# vssb_SMD.net
KiCad netlist of a schematic drawn in EAGLE
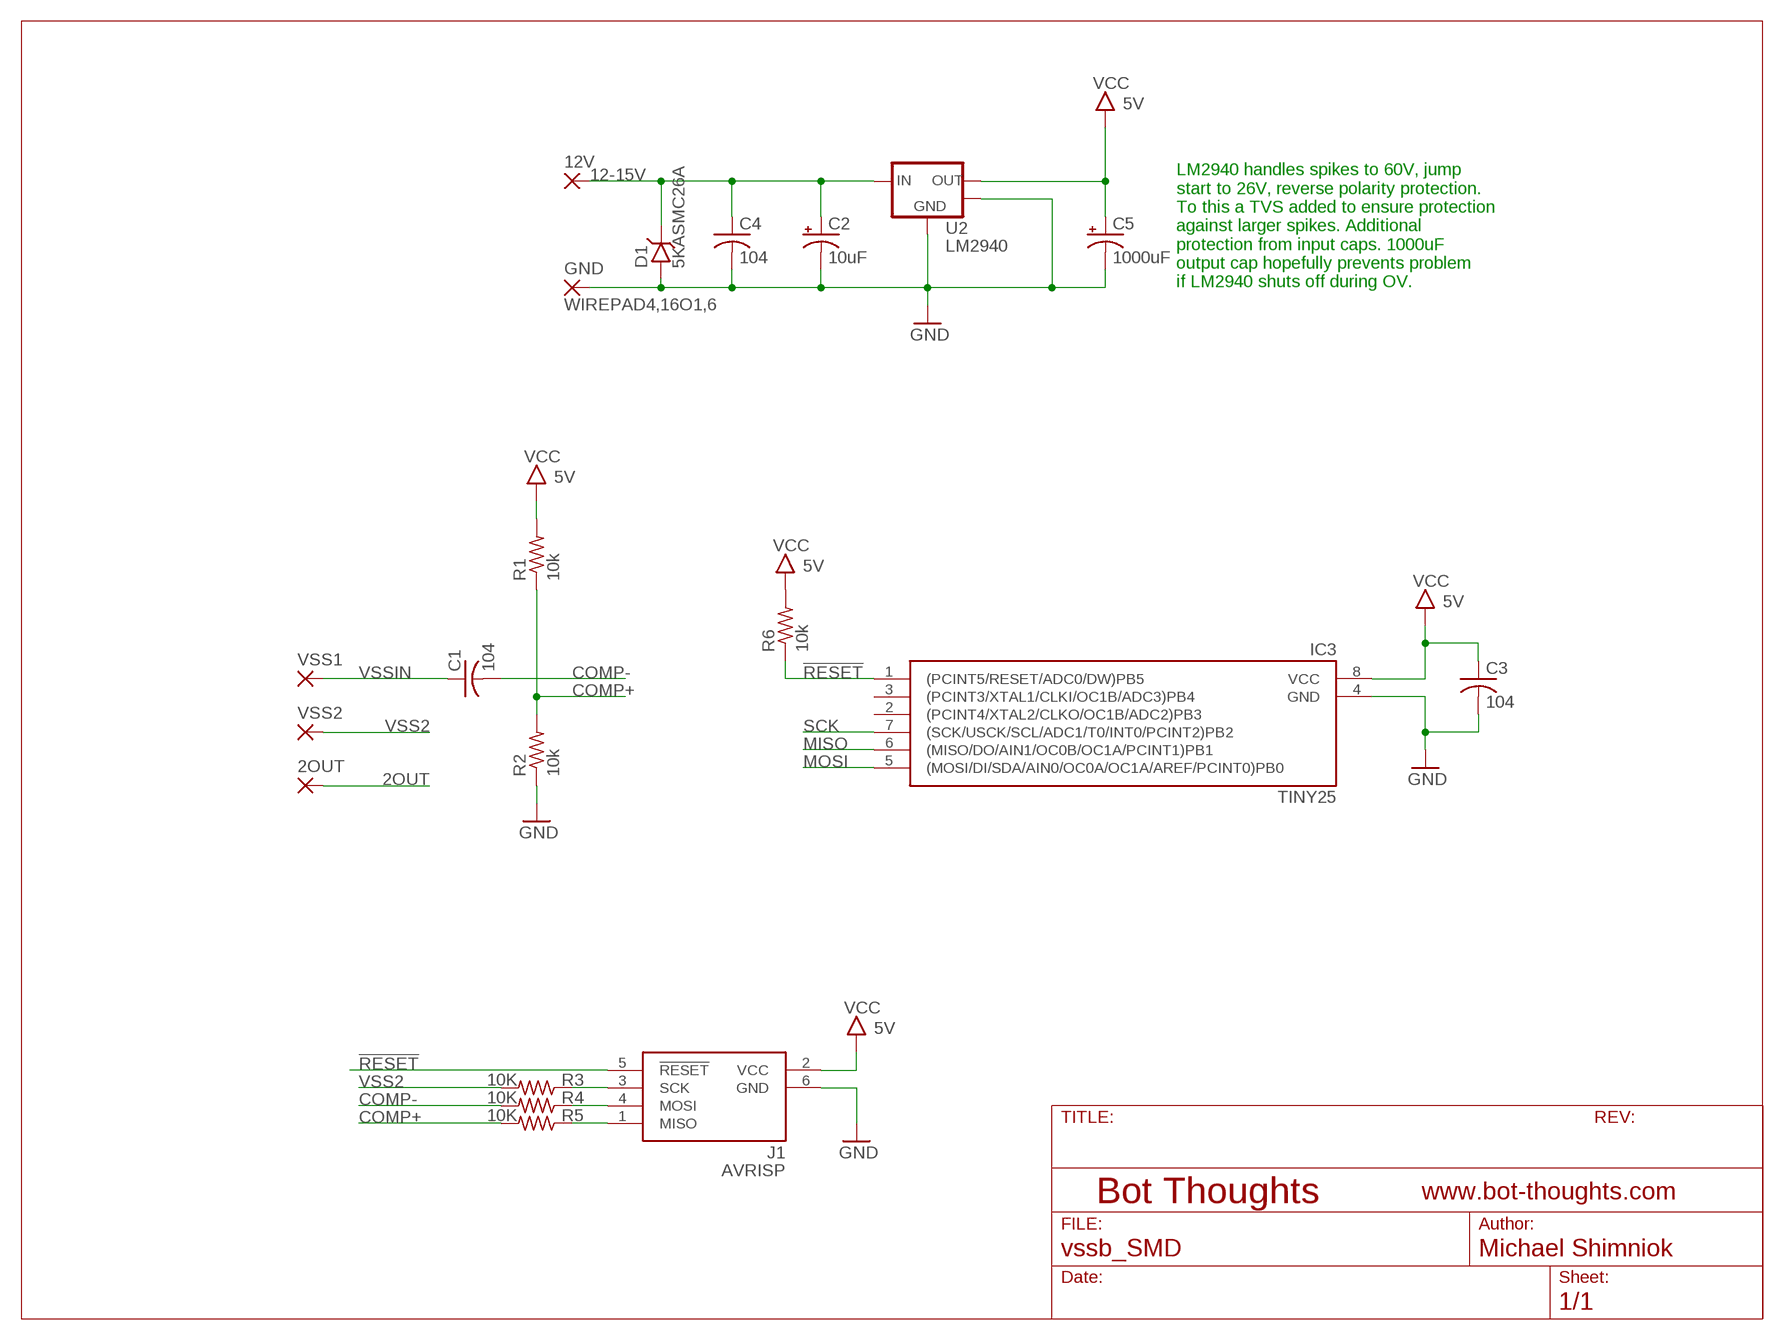
[diagram p0: schematic, sheet 1]

(export (version "E")
  (design (tool "Eeschema 10.0.6"))
  (components
    (comp (ref "2OUT")
      (value "WIREPAD4,16O1,6")
      (footprint "eagle-import:4,16O1,6")
      (libsource (lib "eagle-import") (part "WIREPAD4,16O1,6"))
    )
    (comp (ref "12V")
      (value "WIREPAD4,16O1,6")
      (footprint "eagle-import:4,16O1,6")
      (libsource (lib "eagle-import") (part "WIREPAD4,16O1,6"))
    )
    (comp (ref "C1")
      (value "104")
      (footprint "eagle-import:C0603")
      (libsource (lib "eagle-import") (part "C-USC0603"))
    )
    (comp (ref "C2")
      (value "10uF")
      (footprint "eagle-import:E2,5-6")
      (libsource (lib "eagle-import") (part "CPOL-USE2.5-6"))
    )
    (comp (ref "C3")
      (value "104")
      (footprint "eagle-import:C0603")
      (libsource (lib "eagle-import") (part "C-USC0603"))
    )
    (comp (ref "C4")
      (value "104")
      (footprint "eagle-import:C0603")
      (libsource (lib "eagle-import") (part "C-USC0603"))
    )
    (comp (ref "C5")
      (value "1000uF")
      (footprint "eagle-import:E5-13")
      (libsource (lib "eagle-import") (part "CPOL-USE5-13"))
    )
    (comp (ref "D1")
      (value "5KASMC26A")
      (footprint "eagle-import:DO-214AB")
      (libsource (lib "eagle-import") (part "5KASMC"))
    )
    (comp (ref "GND")
      (value "WIREPAD4,16O1,6")
      (footprint "eagle-import:4,16O1,6")
      (libsource (lib "eagle-import") (part "WIREPAD4,16O1,6"))
    )
    (comp (ref "IC3")
      (value "TINY25")
      (footprint "eagle-import:SOIC8N")
      (libsource (lib "eagle-import") (part "TINY25/45/85-20SSU"))
    )
    (comp (ref "J1")
      (value "AVRISP")
      (footprint "eagle-import:CON6P2R")
      (libsource (lib "eagle-import") (part "AVRISP6_COMPACT"))
    )
    (comp (ref "R1")
      (value "10k")
      (footprint "eagle-import:R0603")
      (libsource (lib "eagle-import") (part "R-US_R0603"))
    )
    (comp (ref "R2")
      (value "10k")
      (footprint "eagle-import:R0603")
      (libsource (lib "eagle-import") (part "R-US_R0603"))
    )
    (comp (ref "R3")
      (value "10K")
      (footprint "eagle-import:R0603")
      (libsource (lib "eagle-import") (part "R-US_R0603"))
    )
    (comp (ref "R4")
      (value "10K")
      (footprint "eagle-import:R0603")
      (libsource (lib "eagle-import") (part "R-US_R0603"))
    )
    (comp (ref "R5")
      (value "10K")
      (footprint "eagle-import:R0603")
      (libsource (lib "eagle-import") (part "R-US_R0603"))
    )
    (comp (ref "R6")
      (value "10k")
      (footprint "eagle-import:R0603")
      (libsource (lib "eagle-import") (part "R-US_R0603"))
    )
    (comp (ref "U2")
      (value "LM2940")
      (footprint "eagle-import:SOT-223-3")
      (libsource (lib "eagle-import") (part "LM2940DCY"))
    )
    (comp (ref "VSS1")
      (value "WIREPAD4,16O1,6")
      (footprint "eagle-import:4,16O1,6")
      (libsource (lib "eagle-import") (part "WIREPAD4,16O1,6"))
    )
    (comp (ref "VSS2")
      (value "WIREPAD4,16O1,6")
      (footprint "eagle-import:4,16O1,6")
      (libsource (lib "eagle-import") (part "WIREPAD4,16O1,6"))
    )
  )
  (nets
    (net (code "1") (name "/2OUT") (class "Default")
      (node (ref "2OUT") (pin "1") (pinfunction "P_1") (pintype "passive"))
    )
    (net (code "2") (name "/12-15V") (class "Default")
      (node (ref "12V") (pin "1") (pinfunction "P_1") (pintype "passive"))
      (node (ref "C2") (pin "+") (pinfunction "+_+") (pintype "passive"))
      (node (ref "C4") (pin "1") (pinfunction "1_1") (pintype "passive"))
      (node (ref "D1") (pin "C") (pinfunction "C_C") (pintype "passive"))
      (node (ref "U2") (pin "1") (pinfunction "VIN_1") (pintype "bidirectional"))
    )
    (net (code "3") (name "/COMP+") (class "Default")
      (node (ref "R1") (pin "1") (pinfunction "1_1") (pintype "passive"))
      (node (ref "R2") (pin "2") (pinfunction "2_2") (pintype "passive"))
      (node (ref "R5") (pin "2") (pinfunction "2_2") (pintype "passive"))
    )
    (net (code "4") (name "/COMP-") (class "Default")
      (node (ref "C1") (pin "2") (pinfunction "2_2") (pintype "passive"))
      (node (ref "R4") (pin "2") (pinfunction "2_2") (pintype "passive"))
    )
    (net (code "5") (name "/MISO") (class "Default")
      (node (ref "IC3") (pin "6") (pinfunction "(MISO/DO/AIN1/OC0B/OC1A/PCINT1)PB1_6") (pintype "bidirectional"))
      (node (ref "J1") (pin "1") (pinfunction "MISO_1") (pintype "input"))
      (node (ref "R5") (pin "1") (pinfunction "1_1") (pintype "passive"))
    )
    (net (code "6") (name "/MOSI") (class "Default")
      (node (ref "IC3") (pin "5") (pinfunction "(MOSI/DI/SDA/AIN0/OC0A/OC1A/AREF/PCINT0)PB0_5") (pintype "bidirectional"))
      (node (ref "J1") (pin "4") (pinfunction "MOSI_4") (pintype "output"))
      (node (ref "R4") (pin "1") (pinfunction "1_1") (pintype "passive"))
    )
    (net (code "7") (name "/SCK") (class "Default")
      (node (ref "IC3") (pin "7") (pinfunction "(SCK/USCK/SCL/ADC1/T0/INT0/PCINT2)PB2_7") (pintype "bidirectional"))
      (node (ref "J1") (pin "3") (pinfunction "SCK_3") (pintype "output"))
      (node (ref "R3") (pin "1") (pinfunction "1_1") (pintype "passive"))
    )
    (net (code "8") (name "/VSS2") (class "Default")
      (node (ref "R3") (pin "2") (pinfunction "2_2") (pintype "passive"))
      (node (ref "VSS2") (pin "1") (pinfunction "P_1") (pintype "passive"))
    )
    (net (code "9") (name "/VSSIN") (class "Default")
      (node (ref "C1") (pin "1") (pinfunction "1_1") (pintype "passive"))
      (node (ref "VSS1") (pin "1") (pinfunction "P_1") (pintype "passive"))
    )
    (net (code "10") (name "/~{RESET}") (class "Default")
      (node (ref "IC3") (pin "1") (pinfunction "(PCINT5/RESET/ADC0/DW)PB5_1") (pintype "bidirectional"))
      (node (ref "J1") (pin "5") (pinfunction "~{RESET}_5") (pintype "output"))
      (node (ref "R6") (pin "1") (pinfunction "1_1") (pintype "passive"))
    )
    (net (code "11") (name "5V") (class "Default")
      (node (ref "C3") (pin "1") (pinfunction "1_1") (pintype "passive"))
      (node (ref "C5") (pin "+") (pinfunction "+_+") (pintype "passive"))
      (node (ref "IC3") (pin "8") (pinfunction "VCC_8") (pintype "power_in"))
      (node (ref "J1") (pin "2") (pinfunction "VCC_2") (pintype "power_in"))
      (node (ref "R1") (pin "2") (pinfunction "2_2") (pintype "passive"))
      (node (ref "R6") (pin "2") (pinfunction "2_2") (pintype "passive"))
      (node (ref "U2") (pin "3") (pinfunction "VOUT_3") (pintype "bidirectional"))
    )
    (net (code "12") (name "GND") (class "Default")
      (node (ref "C2") (pin "-") (pinfunction "-_-") (pintype "passive"))
      (node (ref "C3") (pin "2") (pinfunction "2_2") (pintype "passive"))
      (node (ref "C4") (pin "2") (pinfunction "2_2") (pintype "passive"))
      (node (ref "C5") (pin "-") (pinfunction "-_-") (pintype "passive"))
      (node (ref "D1") (pin "A") (pinfunction "A_A") (pintype "passive"))
      (node (ref "GND") (pin "1") (pinfunction "P_1") (pintype "passive"))
      (node (ref "IC3") (pin "4") (pinfunction "GND_4") (pintype "power_in"))
      (node (ref "J1") (pin "6") (pinfunction "GND_6") (pintype "power_in"))
      (node (ref "R2") (pin "1") (pinfunction "1_1") (pintype "passive"))
      (node (ref "U2") (pin "2") (pinfunction "GND_2") (pintype "bidirectional"))
      (node (ref "U2") (pin "4") (pinfunction "TAB_4") (pintype "bidirectional"))
    )
    (net (code "13") (name "unconnected-(IC3-(PCINT3{slash}XTAL1{slash}CLKI{slash}OC1B{slash}ADC3)PB4-Pad3)") (class "Default")
      (node (ref "IC3") (pin "3") (pinfunction "(PCINT3/XTAL1/CLKI/OC1B/ADC3)PB4_3") (pintype "bidirectional"))
    )
    (net (code "14") (name "unconnected-(IC3-(PCINT4{slash}XTAL2{slash}CLKO{slash}OC1B{slash}ADC2)PB3-Pad2)") (class "Default")
      (node (ref "IC3") (pin "2") (pinfunction "(PCINT4/XTAL2/CLKO/OC1B/ADC2)PB3_2") (pintype "bidirectional"))
    )
  )
)
